# YA-N-Radio.net
KiCad netlist of a schematic drawn in Altium Designer
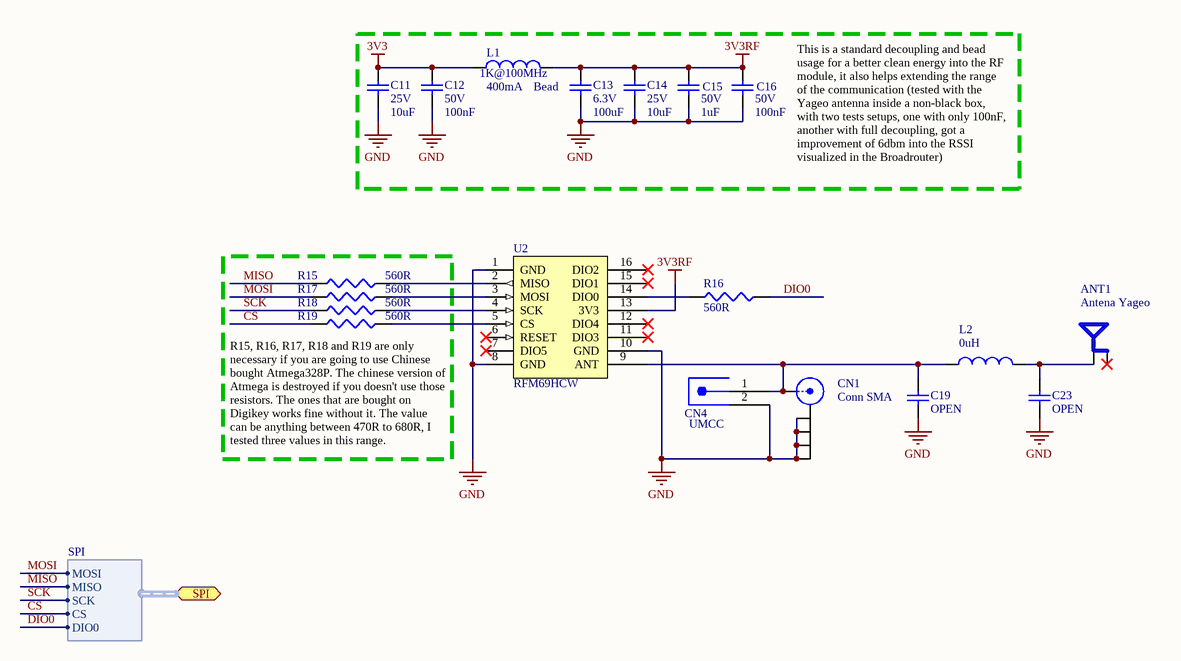
[diagram p0: YA-N-Radio.SchDoc]

(export (version "E")
  (design (tool "Eeschema 10.0.6"))
  (components
    (comp (ref "ANT1")
      (value "Antena Yageo")
      (footprint "ANT1204LL05R0915A")
      (description "Antena YAGEO")
      (fields (field (name "Comment") "Antena"))
      (libsource (lib "Navarro") (part "Antena Yageo 915Mhz"))
    )
    (comp (ref "C11")
      (value "10uF")
      (footprint "CC0805")
      (description "Capacitor (Semiconductor SIM Model)")
      (fields (field (name "TENSÃO") "25V") (field (name "Comment") "Capacitor Cerâmico"))
      (libsource (lib "NavarroCAP") (part "Cap 10uF 25V 0805 X5R"))
    )
    (comp (ref "C12")
      (value "100nF")
      (footprint "CC0603")
      (description "Capacitor (Semiconductor SIM Model)")
      (fields (field (name "TENSÃO") "50V") (field (name "Comment") "Capacitor Cerâmico"))
      (libsource (lib "NavarroCAP") (part "Cap 100nF 50V 0603 X7R"))
    )
    (comp (ref "C13")
      (value "100uF")
      (footprint "CC1206")
      (description "Capacitor (Semiconductor SIM Model)")
      (fields (field (name "TENSÃO") "6.3V") (field (name "Comment") "Capacitor Cerâmico"))
      (libsource (lib "NavarroCAP") (part "Cap 100uF 6.3V 1206 X5R"))
    )
    (comp (ref "C14")
      (value "10uF")
      (footprint "CC0805")
      (description "Capacitor (Semiconductor SIM Model)")
      (fields (field (name "TENSÃO") "25V") (field (name "Comment") "Capacitor Cerâmico"))
      (libsource (lib "NavarroCAP") (part "Cap 10uF 25V 0805 X5R"))
    )
    (comp (ref "C15")
      (value "1uF")
      (footprint "CC0603")
      (description "Capacitor (Semiconductor SIM Model)")
      (fields (field (name "TENSÃO") "50V") (field (name "Comment") "Capacitor Cerâmico"))
      (libsource (lib "NavarroCAP") (part "Cap 1uF 50V 0603 X5R"))
    )
    (comp (ref "C16")
      (value "100nF")
      (footprint "CC0603")
      (description "Capacitor (Semiconductor SIM Model)")
      (fields (field (name "TENSÃO") "50V") (field (name "Comment") "Capacitor Cerâmico"))
      (libsource (lib "NavarroCAP") (part "Cap 100nF 50V 0603 X7R"))
    )
    (comp (ref "C19")
      (value "OPEN")
      (footprint "CC0603")
      (description "Capacitor (Semiconductor SIM Model)")
      (fields (field (name "Comment") "Capacitor Cerâmico"))
      (libsource (lib "NavarroCAP") (part "Cap OPEN 0603"))
    )
    (comp (ref "C23")
      (value "OPEN")
      (footprint "CC0603")
      (description "Capacitor (Semiconductor SIM Model)")
      (fields (field (name "Comment") "Capacitor Cerâmico"))
      (libsource (lib "NavarroCAP") (part "Cap OPEN 0603"))
    )
    (comp (ref "CN1")
      (value "Conn SMA")
      (footprint "CONN SMA-JACK")
      (description "Conector SMA")
      (libsource (lib "NavarroCON") (part "Conn SMA"))
    )
    (comp (ref "CN4")
      (value "UMCC")
      (footprint "CONN U.FL")
      (libsource (lib "NavarroCON") (part "Conn UMCC TE"))
    )
    (comp (ref "L1")
      (value "Bead")
      (footprint "CC0603")
      (fields (field (name "CORRENTE") "400mA") (field (name "ALTIUM_VALUE") "1K@100MHz"))
      (libsource (lib "NavarroIND") (part "Bd 1K@100MHz 0603 400mA"))
    )
    (comp (ref "L2")
      (value "0uH")
      (footprint "CC0603")
      (description "Bead")
      (libsource (lib "NavarroIND") (part "Bd 1K@100MHz 0603 400mA"))
    )
    (comp (ref "R15")
      (value "560R")
      (footprint "CC0603")
      (description "Resistor")
      (libsource (lib "NavarroRES") (part "Res 560R 1% 0603 1/10w"))
    )
    (comp (ref "R16")
      (value "560R")
      (footprint "CC0603")
      (description "Resistor")
      (libsource (lib "NavarroRES") (part "Res 560R 1% 0603 1/10w"))
    )
    (comp (ref "R17")
      (value "560R")
      (footprint "CC0603")
      (description "Resistor")
      (libsource (lib "NavarroRES") (part "Res 560R 1% 0603 1/10w"))
    )
    (comp (ref "R18")
      (value "560R")
      (footprint "CC0603")
      (description "Resistor")
      (libsource (lib "NavarroRES") (part "Res 560R 1% 0603 1/10w"))
    )
    (comp (ref "R19")
      (value "560R")
      (footprint "CC0603")
      (description "Resistor")
      (libsource (lib "NavarroRES") (part "Res 560R 1% 0603 1/10w"))
    )
    (comp (ref "U2")
      (value "RFM69HCW")
      (footprint "RFM69HCW")
      (description "Memória")
      (libsource (lib "Navarro") (part "RFM69HCW"))
    )
  )
  (nets
    (net (code "2") (name "/CS") (class "Default")
      (node (ref "R19") (pin "1") (pinfunction "1_1") (pintype "passive"))
    )
    (net (code "3") (name "/DIO0") (class "Default")
      (node (ref "R16") (pin "2") (pinfunction "2_2") (pintype "passive"))
    )
    (net (code "4") (name "/MISO") (class "Default")
      (node (ref "R15") (pin "1") (pinfunction "1_1") (pintype "passive"))
    )
    (net (code "5") (name "/MOSI") (class "Default")
      (node (ref "R17") (pin "1") (pinfunction "1_1") (pintype "passive"))
    )
    (net (code "6") (name "/SCK") (class "Default")
      (node (ref "R18") (pin "1") (pinfunction "1_1") (pintype "passive"))
    )
    (net (code "8") (name "3V3") (class "Default")
      (node (ref "C11") (pin "2") (pinfunction "2_2") (pintype "passive"))
      (node (ref "C12") (pin "2") (pinfunction "2_2") (pintype "passive"))
      (node (ref "L1") (pin "1") (pinfunction "1_1") (pintype "passive"))
    )
    (net (code "9") (name "3V3RF") (class "Default")
      (node (ref "C13") (pin "2") (pinfunction "2_2") (pintype "passive"))
      (node (ref "C14") (pin "2") (pinfunction "2_2") (pintype "passive"))
      (node (ref "C15") (pin "2") (pinfunction "2_2") (pintype "passive"))
      (node (ref "C16") (pin "2") (pinfunction "2_2") (pintype "passive"))
      (node (ref "L1") (pin "2") (pinfunction "2_2") (pintype "passive"))
      (node (ref "U2") (pin "13") (pinfunction "3V3_13") (pintype "power_in"))
    )
    (net (code "10") (name "GND") (class "Default")
      (node (ref "C11") (pin "1") (pinfunction "1_1") (pintype "passive"))
      (node (ref "C12") (pin "1") (pinfunction "1_1") (pintype "passive"))
      (node (ref "C13") (pin "1") (pinfunction "1_1") (pintype "passive"))
      (node (ref "C14") (pin "1") (pinfunction "1_1") (pintype "passive"))
      (node (ref "C15") (pin "1") (pinfunction "1_1") (pintype "passive"))
      (node (ref "C16") (pin "1") (pinfunction "1_1") (pintype "passive"))
      (node (ref "C19") (pin "1") (pinfunction "1_1") (pintype "passive"))
      (node (ref "C23") (pin "1") (pinfunction "1_1") (pintype "passive"))
      (node (ref "CN1") (pin "2") (pinfunction "Y_2") (pintype "passive"))
      (node (ref "CN1") (pin "3") (pinfunction "Y_3") (pintype "passive"))
      (node (ref "CN1") (pin "4") (pinfunction "Y_4") (pintype "passive"))
      (node (ref "CN1") (pin "5") (pinfunction "Y_5") (pintype "passive"))
      (node (ref "CN4") (pin "2") (pinfunction "2_2") (pintype "passive"))
      (node (ref "U2") (pin "1") (pinfunction "GND_1") (pintype "power_in"))
      (node (ref "U2") (pin "10") (pinfunction "GND_10") (pintype "power_in"))
      (node (ref "U2") (pin "8") (pinfunction "GND_8") (pintype "power_in"))
    )
    (net (code "11") (name "Net-(ANT1-Pad1)") (class "Default")
      (node (ref "ANT1") (pin "1") (pinfunction "1_1") (pintype "passive"))
      (node (ref "C23") (pin "2") (pinfunction "2_2") (pintype "passive"))
      (node (ref "L2") (pin "2") (pinfunction "2_2") (pintype "passive"))
    )
    (net (code "12") (name "Net-(CN1-X)") (class "Default")
      (node (ref "C19") (pin "2") (pinfunction "2_2") (pintype "passive"))
      (node (ref "CN1") (pin "1") (pinfunction "X_1") (pintype "passive"))
      (node (ref "CN4") (pin "1") (pinfunction "1_1") (pintype "passive"))
      (node (ref "L2") (pin "1") (pinfunction "1_1") (pintype "passive"))
      (node (ref "U2") (pin "9") (pinfunction "ANT_9") (pintype "passive"))
    )
    (net (code "13") (name "Net-(U2-CS)") (class "Default")
      (node (ref "R19") (pin "2") (pinfunction "2_2") (pintype "passive"))
      (node (ref "U2") (pin "5") (pinfunction "CS_5") (pintype "input"))
    )
    (net (code "14") (name "Net-(U2-DIO0)") (class "Default")
      (node (ref "R16") (pin "1") (pinfunction "1_1") (pintype "passive"))
      (node (ref "U2") (pin "14") (pinfunction "DIO0_14") (pintype "passive"))
    )
    (net (code "15") (name "Net-(U2-MISO)") (class "Default")
      (node (ref "R15") (pin "2") (pinfunction "2_2") (pintype "passive"))
      (node (ref "U2") (pin "2") (pinfunction "MISO_2") (pintype "output"))
    )
    (net (code "16") (name "Net-(U2-MOSI)") (class "Default")
      (node (ref "R17") (pin "2") (pinfunction "2_2") (pintype "passive"))
      (node (ref "U2") (pin "3") (pinfunction "MOSI_3") (pintype "input"))
    )
    (net (code "17") (name "Net-(U2-SCK)") (class "Default")
      (node (ref "R18") (pin "2") (pinfunction "2_2") (pintype "passive"))
      (node (ref "U2") (pin "4") (pinfunction "SCK_4") (pintype "input"))
    )
    (net (code "18") (name "unconnected-(ANT1-Pad2)") (class "Default")
      (node (ref "ANT1") (pin "2") (pinfunction "2_2") (pintype "passive+no_connect"))
    )
    (net (code "19") (name "unconnected-(U2-DIO1-Pad15)") (class "Default")
      (node (ref "U2") (pin "15") (pinfunction "DIO1_15") (pintype "passive+no_connect"))
    )
    (net (code "20") (name "unconnected-(U2-DIO2-Pad16)") (class "Default")
      (node (ref "U2") (pin "16") (pinfunction "DIO2_16") (pintype "passive+no_connect"))
    )
    (net (code "21") (name "unconnected-(U2-DIO3-Pad11)") (class "Default")
      (node (ref "U2") (pin "11") (pinfunction "DIO3_11") (pintype "passive+no_connect"))
    )
    (net (code "22") (name "unconnected-(U2-DIO4-Pad12)") (class "Default")
      (node (ref "U2") (pin "12") (pinfunction "DIO4_12") (pintype "passive+no_connect"))
    )
    (net (code "23") (name "unconnected-(U2-DIO5-Pad7)") (class "Default")
      (node (ref "U2") (pin "7") (pinfunction "DIO5_7") (pintype "passive+no_connect"))
    )
    (net (code "24") (name "unconnected-(U2-RESET-Pad6)") (class "Default")
      (node (ref "U2") (pin "6") (pinfunction "RESET_6") (pintype "input+no_connect"))
    )
  )
)
